# led.net
KiCad netlist of a schematic drawn in Altium Designer
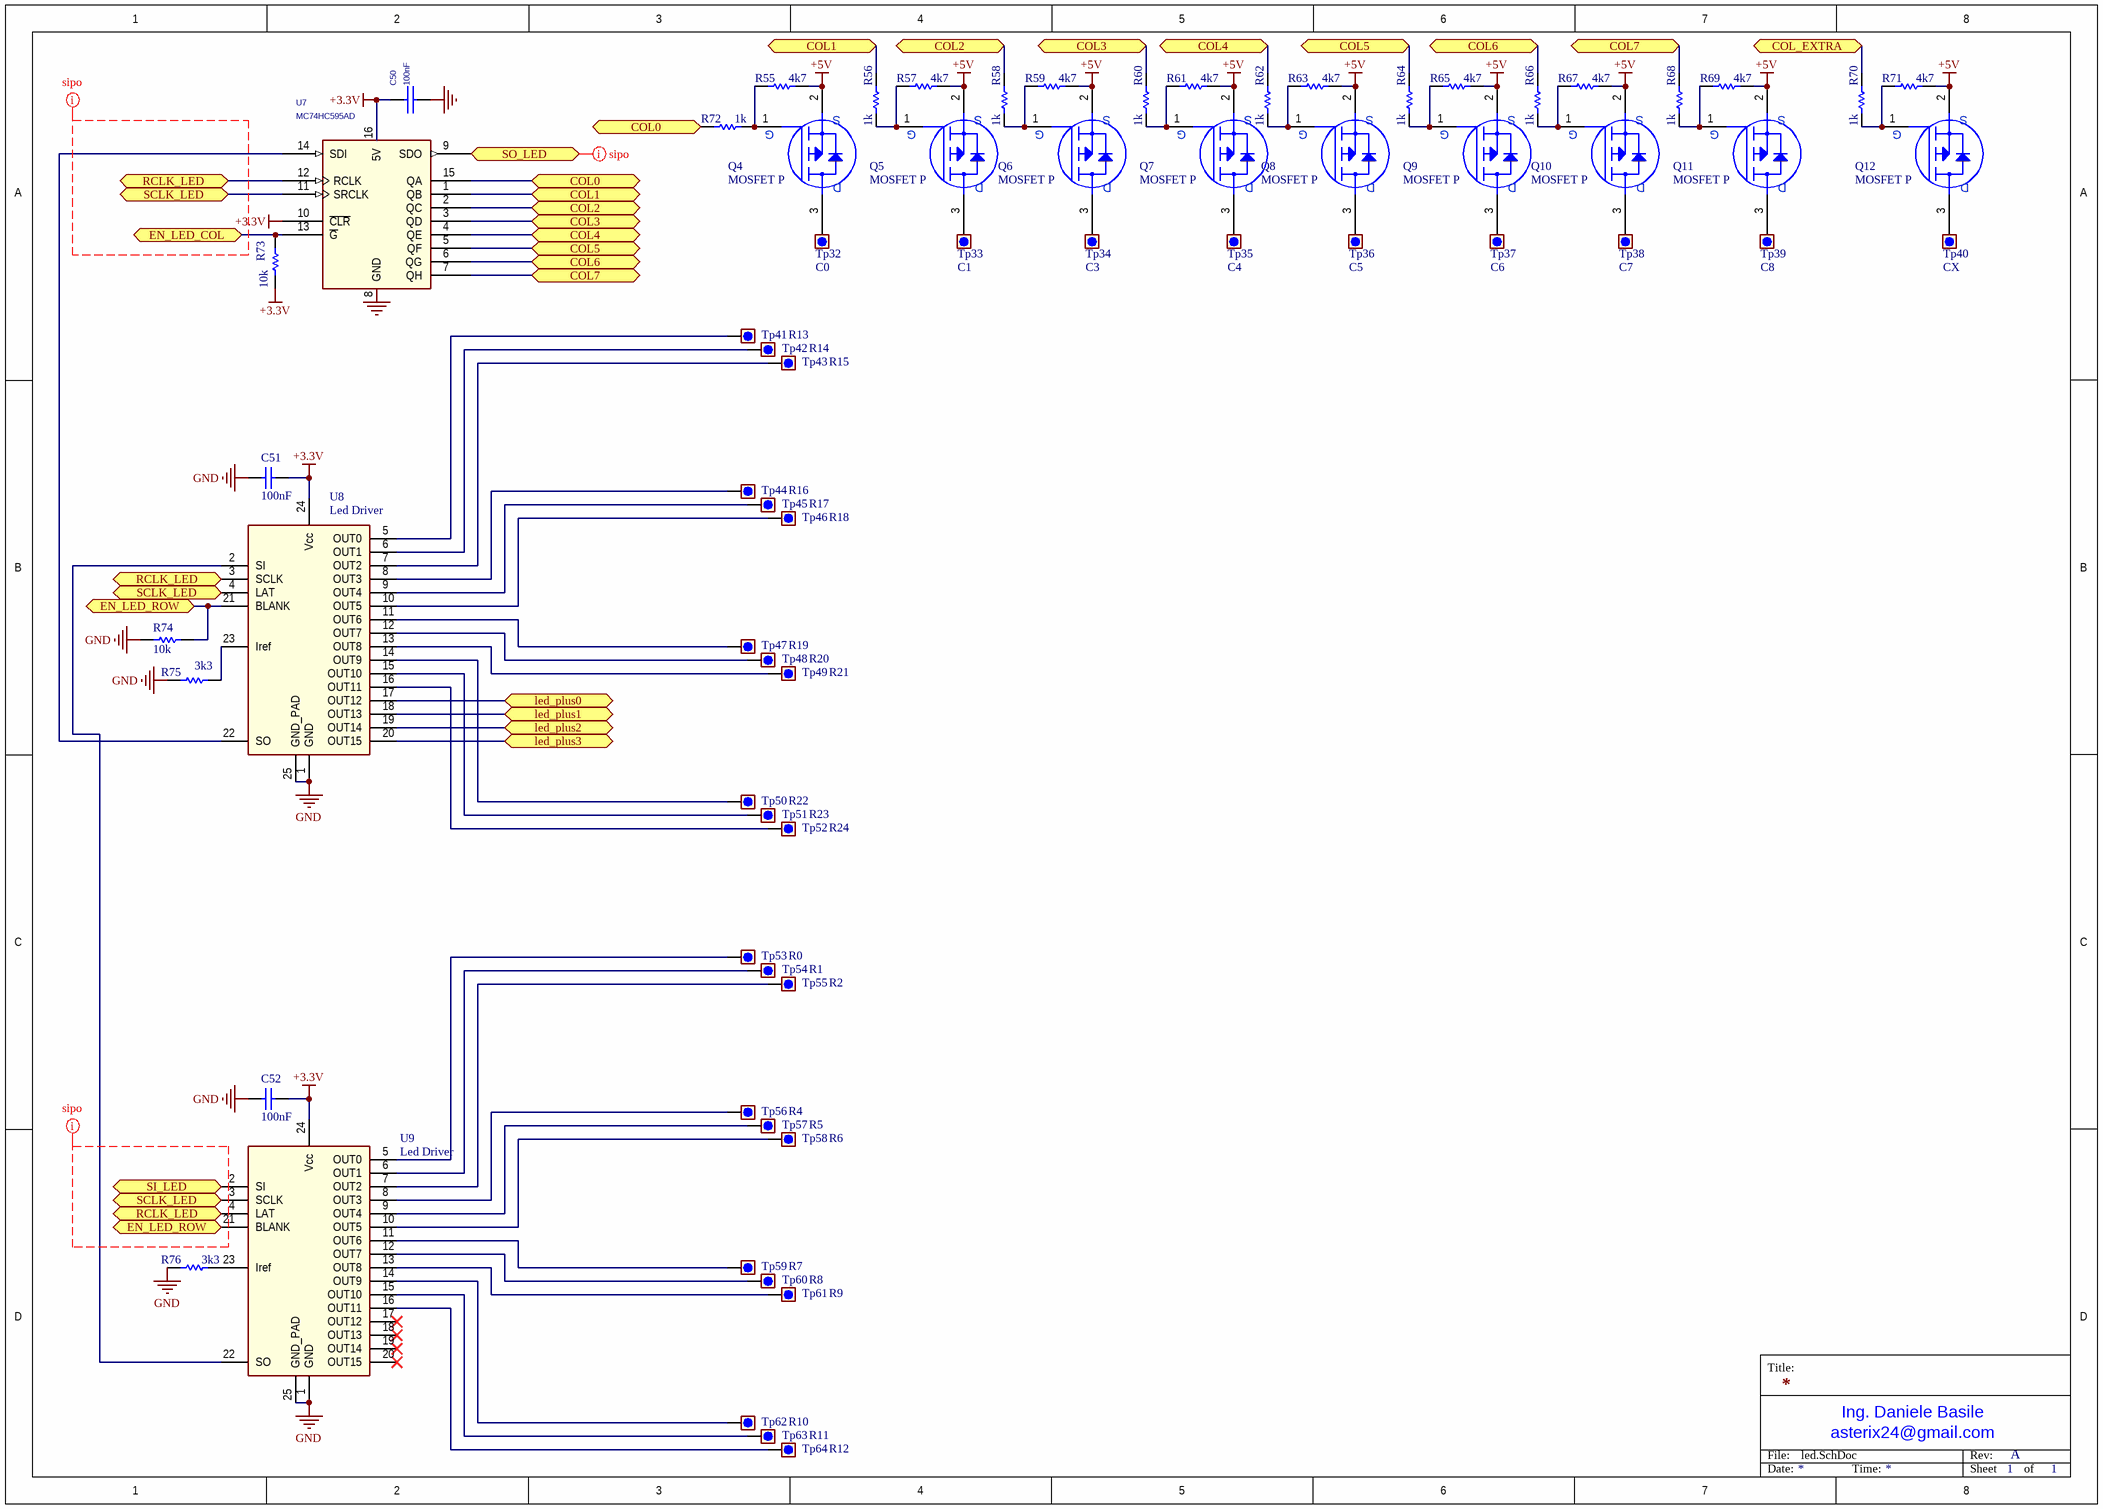
[diagram p0: led.SchDoc]

(export (version "E")
  (design (tool "Eeschema 10.0.6"))
  (components
    (comp (ref "C50")
      (value "100nF")
      (footprint "0603_[1608]")
      (description "CER 50V X7R")
      (libsource (lib "*") (part "C"))
    )
    (comp (ref "C51")
      (value "100nF")
      (footprint "0603_[1608]")
      (description "Ceramic X7R 50V")
      (fields (field (name "PUBLISHER") "Altium Limited"))
      (libsource (lib "DEVELER_Library") (part "Cap"))
    )
    (comp (ref "C52")
      (value "100nF")
      (footprint "0603_[1608]")
      (description "Ceramic X7R 50V")
      (fields (field (name "PUBLISHER") "Altium Limited"))
      (libsource (lib "DEVELER_Library") (part "Cap"))
    )
    (comp (ref "Q4")
      (value "MOSFET P")
      (footprint "SOT-23")
      (description "IRLML5103TRPbF; DMG1013UW;")
      (libsource (lib "develer_library") (part "MOSFET-P 3pin"))
    )
    (comp (ref "Q5")
      (value "MOSFET P")
      (footprint "SOT-23")
      (libsource (lib "develer_library") (part "MOSFET-P 3pin"))
    )
    (comp (ref "Q6")
      (value "MOSFET P")
      (footprint "SOT-23")
      (libsource (lib "develer_library") (part "MOSFET-P 3pin"))
    )
    (comp (ref "Q7")
      (value "MOSFET P")
      (footprint "SOT-23")
      (libsource (lib "develer_library") (part "MOSFET-P 3pin"))
    )
    (comp (ref "Q8")
      (value "MOSFET P")
      (footprint "SOT-23")
      (libsource (lib "develer_library") (part "MOSFET-P 3pin"))
    )
    (comp (ref "Q9")
      (value "MOSFET P")
      (footprint "SOT-23")
      (libsource (lib "develer_library") (part "MOSFET-P 3pin"))
    )
    (comp (ref "Q10")
      (value "MOSFET P")
      (footprint "SOT-23")
      (libsource (lib "develer_library") (part "MOSFET-P 3pin"))
    )
    (comp (ref "Q11")
      (value "MOSFET P")
      (footprint "SOT-23")
      (libsource (lib "develer_library") (part "MOSFET-P 3pin"))
    )
    (comp (ref "Q12")
      (value "MOSFET P")
      (footprint "SOT-23")
      (libsource (lib "develer_library") (part "MOSFET-P 3pin"))
    )
    (comp (ref "R55")
      (value "4k7")
      (footprint "0603_[1608]")
      (description "Resistor")
      (fields (field (name "PUBLISHER") "Altium Limited"))
      (libsource (lib "simboli") (part "Res1"))
    )
    (comp (ref "R56")
      (value "1k")
      (footprint "0603_[1608]")
      (description "Resistor")
      (fields (field (name "PUBLISHER") "Altium Limited"))
      (libsource (lib "simboli") (part "Res1"))
    )
    (comp (ref "R57")
      (value "4k7")
      (footprint "0603_[1608]")
      (description "Resistor")
      (fields (field (name "PUBLISHER") "Altium Limited"))
      (libsource (lib "simboli") (part "Res1"))
    )
    (comp (ref "R58")
      (value "1k")
      (footprint "0603_[1608]")
      (description "Resistor")
      (fields (field (name "PUBLISHER") "Altium Limited"))
      (libsource (lib "simboli") (part "Res1"))
    )
    (comp (ref "R59")
      (value "4k7")
      (footprint "0603_[1608]")
      (description "Resistor")
      (fields (field (name "PUBLISHER") "Altium Limited"))
      (libsource (lib "simboli") (part "Res1"))
    )
    (comp (ref "R60")
      (value "1k")
      (footprint "0603_[1608]")
      (description "Resistor")
      (fields (field (name "PUBLISHER") "Altium Limited"))
      (libsource (lib "simboli") (part "Res1"))
    )
    (comp (ref "R61")
      (value "4k7")
      (footprint "0603_[1608]")
      (description "Resistor")
      (fields (field (name "PUBLISHER") "Altium Limited"))
      (libsource (lib "simboli") (part "Res1"))
    )
    (comp (ref "R62")
      (value "1k")
      (footprint "0603_[1608]")
      (description "Resistor")
      (fields (field (name "PUBLISHER") "Altium Limited"))
      (libsource (lib "simboli") (part "Res1"))
    )
    (comp (ref "R63")
      (value "4k7")
      (footprint "0603_[1608]")
      (description "Resistor")
      (fields (field (name "PUBLISHER") "Altium Limited"))
      (libsource (lib "simboli") (part "Res1"))
    )
    (comp (ref "R64")
      (value "1k")
      (footprint "0603_[1608]")
      (description "Resistor")
      (fields (field (name "PUBLISHER") "Altium Limited"))
      (libsource (lib "simboli") (part "Res1"))
    )
    (comp (ref "R65")
      (value "4k7")
      (footprint "0603_[1608]")
      (description "Resistor")
      (fields (field (name "PUBLISHER") "Altium Limited"))
      (libsource (lib "simboli") (part "Res1"))
    )
    (comp (ref "R66")
      (value "1k")
      (footprint "0603_[1608]")
      (description "Resistor")
      (fields (field (name "PUBLISHER") "Altium Limited"))
      (libsource (lib "simboli") (part "Res1"))
    )
    (comp (ref "R67")
      (value "4k7")
      (footprint "0603_[1608]")
      (description "Resistor")
      (fields (field (name "PUBLISHER") "Altium Limited"))
      (libsource (lib "simboli") (part "Res1"))
    )
    (comp (ref "R68")
      (value "1k")
      (footprint "0603_[1608]")
      (description "Resistor")
      (fields (field (name "PUBLISHER") "Altium Limited"))
      (libsource (lib "simboli") (part "Res1"))
    )
    (comp (ref "R69")
      (value "4k7")
      (footprint "0603_[1608]")
      (description "Resistor")
      (fields (field (name "PUBLISHER") "Altium Limited"))
      (libsource (lib "simboli") (part "Res1"))
    )
    (comp (ref "R70")
      (value "1k")
      (footprint "0603_[1608]")
      (description "Resistor")
      (fields (field (name "PUBLISHER") "Altium Limited"))
      (libsource (lib "simboli") (part "Res1"))
    )
    (comp (ref "R71")
      (value "4k7")
      (footprint "0603_[1608]")
      (description "Resistor")
      (fields (field (name "PUBLISHER") "Altium Limited"))
      (libsource (lib "simboli") (part "Res1"))
    )
    (comp (ref "R72")
      (value "1k")
      (footprint "0603_[1608]")
      (description "Resistor")
      (fields (field (name "PUBLISHER") "Altium Limited"))
      (libsource (lib "simboli") (part "Res1"))
    )
    (comp (ref "R73")
      (value "10k")
      (footprint "0603_[1608]")
      (description "Resistor")
      (fields (field (name "PUBLISHER") "Altium Limited"))
      (libsource (lib "simboli") (part "Res1"))
    )
    (comp (ref "R74")
      (value "10k")
      (footprint "0603_[1608]")
      (description "Resistor")
      (fields (field (name "PUBLISHER") "Altium Limited"))
      (libsource (lib "simboli") (part "Res1"))
    )
    (comp (ref "R75")
      (value "3k3")
      (footprint "0805_[2012]")
      (description "Resistor")
      (fields (field (name "PUBLISHER") "Altium Limited"))
      (libsource (lib "simboli") (part "Res1"))
    )
    (comp (ref "R76")
      (value "3k3")
      (footprint "0805_[2012]")
      (description "Resistor")
      (fields (field (name "PUBLISHER") "Altium Limited"))
      (libsource (lib "simboli") (part "Res1"))
    )
    (comp (ref "Tp32")
      (value "C0")
      (footprint "TEST_POINT_THD_D1.6mm_oval")
      (description "Test point")
      (libsource (lib "") (part "Test_point_1"))
    )
    (comp (ref "Tp33")
      (value "C1")
      (footprint "TEST_POINT_THD_D1.6mm_oval")
      (description "Test point")
      (libsource (lib "") (part "Test_point_1"))
    )
    (comp (ref "Tp34")
      (value "C3")
      (footprint "TEST_POINT_THD_D1.6mm_oval")
      (description "Test point")
      (libsource (lib "") (part "Test_point_1"))
    )
    (comp (ref "Tp35")
      (value "C4")
      (footprint "TEST_POINT_THD_D1.6mm_oval")
      (description "Test point")
      (libsource (lib "") (part "Test_point_1"))
    )
    (comp (ref "Tp36")
      (value "C5")
      (footprint "TEST_POINT_THD_D1.6mm_oval")
      (description "Test point")
      (libsource (lib "") (part "Test_point_1"))
    )
    (comp (ref "Tp37")
      (value "C6")
      (footprint "TEST_POINT_THD_D1.6mm_oval")
      (description "Test point")
      (libsource (lib "") (part "Test_point_1"))
    )
    (comp (ref "Tp38")
      (value "C7")
      (footprint "TEST_POINT_THD_D1.6mm_oval")
      (description "Test point")
      (libsource (lib "") (part "Test_point_1"))
    )
    (comp (ref "Tp39")
      (value "C8")
      (footprint "TEST_POINT_THD_D1.6mm_oval")
      (description "Test point")
      (libsource (lib "") (part "Test_point_1"))
    )
    (comp (ref "Tp40")
      (value "CX")
      (footprint "TEST_POINT_THD_D1.6mm_oval")
      (description "Test point")
      (libsource (lib "") (part "Test_point_1"))
    )
    (comp (ref "Tp41")
      (value "R13")
      (footprint "TEST_POINT_THD_D1.6mm_oval")
      (description "Test point")
      (libsource (lib "DEVELER_Library") (part "Test_point"))
    )
    (comp (ref "Tp42")
      (value "R14")
      (footprint "TEST_POINT_THD_D1.6mm_oval")
      (description "Test point")
      (libsource (lib "DEVELER_Library") (part "Test_point"))
    )
    (comp (ref "Tp43")
      (value "R15")
      (footprint "TEST_POINT_THD_D1.6mm_oval")
      (description "Test point")
      (libsource (lib "DEVELER_Library") (part "Test_point"))
    )
    (comp (ref "Tp44")
      (value "R16")
      (footprint "TEST_POINT_THD_D1.6mm_oval")
      (description "Test point")
      (libsource (lib "DEVELER_Library") (part "Test_point"))
    )
    (comp (ref "Tp45")
      (value "R17")
      (footprint "TEST_POINT_THD_D1.6mm_oval")
      (description "Test point")
      (libsource (lib "DEVELER_Library") (part "Test_point"))
    )
    (comp (ref "Tp46")
      (value "R18")
      (footprint "TEST_POINT_THD_D1.6mm_oval")
      (description "Test point")
      (libsource (lib "DEVELER_Library") (part "Test_point"))
    )
    (comp (ref "Tp47")
      (value "R19")
      (footprint "TEST_POINT_THD_D1.6mm_oval")
      (description "Test point")
      (libsource (lib "DEVELER_Library") (part "Test_point"))
    )
    (comp (ref "Tp48")
      (value "R20")
      (footprint "TEST_POINT_THD_D1.6mm_oval")
      (description "Test point")
      (libsource (lib "DEVELER_Library") (part "Test_point"))
    )
    (comp (ref "Tp49")
      (value "R21")
      (footprint "TEST_POINT_THD_D1.6mm_oval")
      (description "Test point")
      (libsource (lib "DEVELER_Library") (part "Test_point"))
    )
    (comp (ref "Tp50")
      (value "R22")
      (footprint "TEST_POINT_THD_D1.6mm_oval")
      (description "Test point")
      (libsource (lib "DEVELER_Library") (part "Test_point"))
    )
    (comp (ref "Tp51")
      (value "R23")
      (footprint "TEST_POINT_THD_D1.6mm_oval")
      (description "Test point")
      (libsource (lib "DEVELER_Library") (part "Test_point"))
    )
    (comp (ref "Tp52")
      (value "R24")
      (footprint "TEST_POINT_THD_D1.6mm_oval")
      (description "Test point")
      (libsource (lib "DEVELER_Library") (part "Test_point"))
    )
    (comp (ref "Tp53")
      (value "R0")
      (footprint "TEST_POINT_THD_D1.6mm_oval")
      (description "Test point")
      (libsource (lib "DEVELER_Library") (part "Test_point"))
    )
    (comp (ref "Tp54")
      (value "R1")
      (footprint "TEST_POINT_THD_D1.6mm_oval")
      (description "Test point")
      (libsource (lib "DEVELER_Library") (part "Test_point"))
    )
    (comp (ref "Tp55")
      (value "R2")
      (footprint "TEST_POINT_THD_D1.6mm_oval")
      (description "Test point")
      (libsource (lib "DEVELER_Library") (part "Test_point"))
    )
    (comp (ref "Tp56")
      (value "R4")
      (footprint "TEST_POINT_THD_D1.6mm_oval")
      (description "Test point")
      (libsource (lib "DEVELER_Library") (part "Test_point"))
    )
    (comp (ref "Tp57")
      (value "R5")
      (footprint "TEST_POINT_THD_D1.6mm_oval")
      (description "Test point")
      (libsource (lib "DEVELER_Library") (part "Test_point"))
    )
    (comp (ref "Tp58")
      (value "R6")
      (footprint "TEST_POINT_THD_D1.6mm_oval")
      (description "Test point")
      (libsource (lib "DEVELER_Library") (part "Test_point"))
    )
    (comp (ref "Tp59")
      (value "R7")
      (footprint "TEST_POINT_THD_D1.6mm_oval")
      (description "Test point")
      (libsource (lib "DEVELER_Library") (part "Test_point"))
    )
    (comp (ref "Tp60")
      (value "R8")
      (footprint "TEST_POINT_THD_D1.6mm_oval")
      (description "Test point")
      (libsource (lib "DEVELER_Library") (part "Test_point"))
    )
    (comp (ref "Tp61")
      (value "R9")
      (footprint "TEST_POINT_THD_D1.6mm_oval")
      (description "Test point")
      (libsource (lib "DEVELER_Library") (part "Test_point"))
    )
    (comp (ref "Tp62")
      (value "R10")
      (footprint "TEST_POINT_THD_D1.6mm_oval")
      (description "Test point")
      (libsource (lib "DEVELER_Library") (part "Test_point"))
    )
    (comp (ref "Tp63")
      (value "R11")
      (footprint "TEST_POINT_THD_D1.6mm_oval")
      (description "Test point")
      (libsource (lib "DEVELER_Library") (part "Test_point"))
    )
    (comp (ref "Tp64")
      (value "R12")
      (footprint "TEST_POINT_THD_D1.6mm_oval")
      (description "Test point")
      (libsource (lib "DEVELER_Library") (part "Test_point"))
    )
    (comp (ref "U7")
      (value "MC74HC595AD")
      (footprint "SOIC16")
      (description "8-Bit Serial-Input/Serial or Prallel-Output Shift Register with Latched 3-State Outputs")
      (libsource (lib "*") (part "74HC595_27"))
    )
    (comp (ref "U8")
      (value "Led Driver")
      (footprint "TSOP65P640X120_HS-25N")
      (description "(Texas TLC5928; ST STP16CP05)")
      (libsource (lib "develer_library") (part "Led_driver"))
    )
    (comp (ref "U9")
      (value "Led Driver")
      (footprint "TSOP65P640X120_HS-25N")
      (description "(Texas TLC5928; ST STP16CP05)")
      (libsource (lib "develer_library") (part "Led_driver"))
    )
  )
  (nets
    (net (code "1") (name "+3.3V") (class "Default")
      (node (ref "C50") (pin "1") (pinfunction "1_1") (pintype "passive"))
      (node (ref "C51") (pin "2") (pinfunction "2_2") (pintype "passive"))
      (node (ref "C52") (pin "2") (pinfunction "2_2") (pintype "passive"))
      (node (ref "R73") (pin "1") (pinfunction "1_1") (pintype "passive"))
      (node (ref "U7") (pin "10") (pinfunction "~{CLR}_10") (pintype "passive"))
      (node (ref "U7") (pin "16") (pinfunction "5V_16") (pintype "power_in"))
      (node (ref "U8") (pin "24") (pinfunction "Vcc_24") (pintype "passive"))
      (node (ref "U9") (pin "24") (pinfunction "Vcc_24") (pintype "passive"))
    )
    (net (code "2") (name "+5V") (class "Default")
      (node (ref "Q10") (pin "2") (pinfunction "S_2") (pintype "passive"))
      (node (ref "Q11") (pin "2") (pinfunction "S_2") (pintype "passive"))
      (node (ref "Q12") (pin "2") (pinfunction "S_2") (pintype "passive"))
      (node (ref "Q4") (pin "2") (pinfunction "S_2") (pintype "passive"))
      (node (ref "Q5") (pin "2") (pinfunction "S_2") (pintype "passive"))
      (node (ref "Q6") (pin "2") (pinfunction "S_2") (pintype "passive"))
      (node (ref "Q7") (pin "2") (pinfunction "S_2") (pintype "passive"))
      (node (ref "Q8") (pin "2") (pinfunction "S_2") (pintype "passive"))
      (node (ref "Q9") (pin "2") (pinfunction "S_2") (pintype "passive"))
      (node (ref "R55") (pin "1") (pinfunction "1_1") (pintype "passive"))
      (node (ref "R57") (pin "1") (pinfunction "1_1") (pintype "passive"))
      (node (ref "R59") (pin "1") (pinfunction "1_1") (pintype "passive"))
      (node (ref "R61") (pin "1") (pinfunction "1_1") (pintype "passive"))
      (node (ref "R63") (pin "1") (pinfunction "1_1") (pintype "passive"))
      (node (ref "R65") (pin "1") (pinfunction "1_1") (pintype "passive"))
      (node (ref "R67") (pin "1") (pinfunction "1_1") (pintype "passive"))
      (node (ref "R69") (pin "1") (pinfunction "1_1") (pintype "passive"))
      (node (ref "R71") (pin "1") (pinfunction "1_1") (pintype "passive"))
    )
    (net (code "3") (name "/COL0") (class "Default")
      (node (ref "R72") (pin "2") (pinfunction "2_2") (pintype "passive"))
      (node (ref "U7") (pin "15") (pinfunction "QA_15") (pintype "tri_state"))
    )
    (net (code "4") (name "/COL1") (class "Default")
      (node (ref "R56") (pin "1") (pinfunction "1_1") (pintype "passive"))
      (node (ref "U7") (pin "1") (pinfunction "QB_1") (pintype "tri_state"))
    )
    (net (code "5") (name "/COL2") (class "Default")
      (node (ref "R58") (pin "1") (pinfunction "1_1") (pintype "passive"))
      (node (ref "U7") (pin "2") (pinfunction "QC_2") (pintype "tri_state"))
    )
    (net (code "6") (name "/COL3") (class "Default")
      (node (ref "R60") (pin "1") (pinfunction "1_1") (pintype "passive"))
      (node (ref "U7") (pin "3") (pinfunction "QD_3") (pintype "tri_state"))
    )
    (net (code "7") (name "/COL4") (class "Default")
      (node (ref "R62") (pin "1") (pinfunction "1_1") (pintype "passive"))
      (node (ref "U7") (pin "4") (pinfunction "QE_4") (pintype "tri_state"))
    )
    (net (code "8") (name "/COL5") (class "Default")
      (node (ref "R64") (pin "1") (pinfunction "1_1") (pintype "passive"))
      (node (ref "U7") (pin "5") (pinfunction "QF_5") (pintype "tri_state"))
    )
    (net (code "9") (name "/COL6") (class "Default")
      (node (ref "R66") (pin "1") (pinfunction "1_1") (pintype "passive"))
      (node (ref "U7") (pin "6") (pinfunction "QG_6") (pintype "tri_state"))
    )
    (net (code "10") (name "/COL7") (class "Default")
      (node (ref "R68") (pin "1") (pinfunction "1_1") (pintype "passive"))
      (node (ref "U7") (pin "7") (pinfunction "QH_7") (pintype "tri_state"))
    )
    (net (code "11") (name "/COL_EXTRA") (class "Default")
      (node (ref "R70") (pin "1") (pinfunction "1_1") (pintype "passive"))
    )
    (net (code "12") (name "/EN_LED_COL") (class "Default")
      (node (ref "R73") (pin "2") (pinfunction "2_2") (pintype "passive"))
      (node (ref "U7") (pin "13") (pinfunction "~{G}_13") (pintype "passive"))
    )
    (net (code "13") (name "/EN_LED_ROW") (class "Default")
      (node (ref "R74") (pin "2") (pinfunction "2_2") (pintype "passive"))
      (node (ref "U8") (pin "21") (pinfunction "BLANK_21") (pintype "passive"))
      (node (ref "U9") (pin "21") (pinfunction "BLANK_21") (pintype "passive"))
    )
    (net (code "14") (name "/RCLK_LED") (class "Default")
      (node (ref "U7") (pin "12") (pinfunction "RCLK_12") (pintype "input"))
      (node (ref "U8") (pin "3") (pinfunction "SCLK_3") (pintype "passive"))
      (node (ref "U9") (pin "4") (pinfunction "LAT_4") (pintype "passive"))
    )
    (net (code "15") (name "/SCLK_LED") (class "Default")
      (node (ref "U7") (pin "11") (pinfunction "SRCLK_11") (pintype "input"))
      (node (ref "U8") (pin "4") (pinfunction "LAT_4") (pintype "passive"))
      (node (ref "U9") (pin "3") (pinfunction "SCLK_3") (pintype "passive"))
    )
    (net (code "16") (name "/SI_LED") (class "Default")
      (node (ref "U9") (pin "2") (pinfunction "SI_2") (pintype "passive"))
    )
    (net (code "17") (name "/SO_LED") (class "Default")
      (node (ref "U7") (pin "9") (pinfunction "SDO_9") (pintype "output"))
    )
    (net (code "18") (name "/led_plus0") (class "Default")
      (node (ref "U8") (pin "17") (pinfunction "OUT12_17") (pintype "passive"))
    )
    (net (code "19") (name "/led_plus1") (class "Default")
      (node (ref "U8") (pin "18") (pinfunction "OUT13_18") (pintype "passive"))
    )
    (net (code "20") (name "/led_plus2") (class "Default")
      (node (ref "U8") (pin "19") (pinfunction "OUT14_19") (pintype "passive"))
    )
    (net (code "21") (name "/led_plus3") (class "Default")
      (node (ref "U8") (pin "20") (pinfunction "OUT15_20") (pintype "passive"))
    )
    (net (code "22") (name "GND") (class "Default")
      (node (ref "C50") (pin "2") (pinfunction "2_2") (pintype "passive"))
      (node (ref "C51") (pin "1") (pinfunction "1_1") (pintype "passive"))
      (node (ref "C52") (pin "1") (pinfunction "1_1") (pintype "passive"))
      (node (ref "R74") (pin "1") (pinfunction "1_1") (pintype "passive"))
      (node (ref "R75") (pin "1") (pinfunction "1_1") (pintype "passive"))
      (node (ref "R76") (pin "1") (pinfunction "1_1") (pintype "passive"))
      (node (ref "U7") (pin "8") (pinfunction "GND_8") (pintype "power_in"))
      (node (ref "U8") (pin "1") (pinfunction "GND_1") (pintype "passive"))
      (node (ref "U8") (pin "25") (pinfunction "GND_PAD_25") (pintype "passive"))
      (node (ref "U9") (pin "1") (pinfunction "GND_1") (pintype "passive"))
      (node (ref "U9") (pin "25") (pinfunction "GND_PAD_25") (pintype "passive"))
    )
    (net (code "23") (name "Net-(Q4-D)") (class "Default")
      (node (ref "Q4") (pin "3") (pinfunction "D_3") (pintype "passive"))
      (node (ref "Tp32") (pin "1") (pinfunction "1_1") (pintype "passive"))
    )
    (net (code "24") (name "Net-(Q4-G)") (class "Default")
      (node (ref "Q4") (pin "1") (pinfunction "G_1") (pintype "passive"))
      (node (ref "R55") (pin "2") (pinfunction "2_2") (pintype "passive"))
      (node (ref "R72") (pin "1") (pinfunction "1_1") (pintype "passive"))
    )
    (net (code "25") (name "Net-(Q5-D)") (class "Default")
      (node (ref "Q5") (pin "3") (pinfunction "D_3") (pintype "passive"))
      (node (ref "Tp33") (pin "1") (pinfunction "1_1") (pintype "passive"))
    )
    (net (code "26") (name "Net-(Q5-G)") (class "Default")
      (node (ref "Q5") (pin "1") (pinfunction "G_1") (pintype "passive"))
      (node (ref "R56") (pin "2") (pinfunction "2_2") (pintype "passive"))
      (node (ref "R57") (pin "2") (pinfunction "2_2") (pintype "passive"))
    )
    (net (code "27") (name "Net-(Q6-D)") (class "Default")
      (node (ref "Q6") (pin "3") (pinfunction "D_3") (pintype "passive"))
      (node (ref "Tp34") (pin "1") (pinfunction "1_1") (pintype "passive"))
    )
    (net (code "28") (name "Net-(Q6-G)") (class "Default")
      (node (ref "Q6") (pin "1") (pinfunction "G_1") (pintype "passive"))
      (node (ref "R58") (pin "2") (pinfunction "2_2") (pintype "passive"))
      (node (ref "R59") (pin "2") (pinfunction "2_2") (pintype "passive"))
    )
    (net (code "29") (name "Net-(Q7-D)") (class "Default")
      (node (ref "Q7") (pin "3") (pinfunction "D_3") (pintype "passive"))
      (node (ref "Tp35") (pin "1") (pinfunction "1_1") (pintype "passive"))
    )
    (net (code "30") (name "Net-(Q7-G)") (class "Default")
      (node (ref "Q7") (pin "1") (pinfunction "G_1") (pintype "passive"))
      (node (ref "R60") (pin "2") (pinfunction "2_2") (pintype "passive"))
      (node (ref "R61") (pin "2") (pinfunction "2_2") (pintype "passive"))
    )
    (net (code "31") (name "Net-(Q8-D)") (class "Default")
      (node (ref "Q8") (pin "3") (pinfunction "D_3") (pintype "passive"))
      (node (ref "Tp36") (pin "1") (pinfunction "1_1") (pintype "passive"))
    )
    (net (code "32") (name "Net-(Q8-G)") (class "Default")
      (node (ref "Q8") (pin "1") (pinfunction "G_1") (pintype "passive"))
      (node (ref "R62") (pin "2") (pinfunction "2_2") (pintype "passive"))
      (node (ref "R63") (pin "2") (pinfunction "2_2") (pintype "passive"))
    )
    (net (code "33") (name "Net-(Q9-D)") (class "Default")
      (node (ref "Q9") (pin "3") (pinfunction "D_3") (pintype "passive"))
      (node (ref "Tp37") (pin "1") (pinfunction "1_1") (pintype "passive"))
    )
    (net (code "34") (name "Net-(Q9-G)") (class "Default")
      (node (ref "Q9") (pin "1") (pinfunction "G_1") (pintype "passive"))
      (node (ref "R64") (pin "2") (pinfunction "2_2") (pintype "passive"))
      (node (ref "R65") (pin "2") (pinfunction "2_2") (pintype "passive"))
    )
    (net (code "35") (name "Net-(Q10-D)") (class "Default")
      (node (ref "Q10") (pin "3") (pinfunction "D_3") (pintype "passive"))
      (node (ref "Tp38") (pin "1") (pinfunction "1_1") (pintype "passive"))
    )
    (net (code "36") (name "Net-(Q10-G)") (class "Default")
      (node (ref "Q10") (pin "1") (pinfunction "G_1") (pintype "passive"))
      (node (ref "R66") (pin "2") (pinfunction "2_2") (pintype "passive"))
      (node (ref "R67") (pin "2") (pinfunction "2_2") (pintype "passive"))
    )
    (net (code "37") (name "Net-(Q11-D)") (class "Default")
      (node (ref "Q11") (pin "3") (pinfunction "D_3") (pintype "passive"))
      (node (ref "Tp39") (pin "1") (pinfunction "1_1") (pintype "passive"))
    )
    (net (code "38") (name "Net-(Q11-G)") (class "Default")
      (node (ref "Q11") (pin "1") (pinfunction "G_1") (pintype "passive"))
      (node (ref "R68") (pin "2") (pinfunction "2_2") (pintype "passive"))
      (node (ref "R69") (pin "2") (pinfunction "2_2") (pintype "passive"))
    )
    (net (code "39") (name "Net-(Q12-D)") (class "Default")
      (node (ref "Q12") (pin "3") (pinfunction "D_3") (pintype "passive"))
      (node (ref "Tp40") (pin "1") (pinfunction "1_1") (pintype "passive"))
    )
    (net (code "40") (name "Net-(Q12-G)") (class "Default")
      (node (ref "Q12") (pin "1") (pinfunction "G_1") (pintype "passive"))
      (node (ref "R70") (pin "2") (pinfunction "2_2") (pintype "passive"))
      (node (ref "R71") (pin "2") (pinfunction "2_2") (pintype "passive"))
    )
    (net (code "41") (name "Net-(U7-SDI)") (class "Default")
      (node (ref "U7") (pin "14") (pinfunction "SDI_14") (pintype "input"))
      (node (ref "U8") (pin "22") (pinfunction "SO_22") (pintype "passive"))
    )
    (net (code "42") (name "Net-(U8-Iref)") (class "Default")
      (node (ref "R75") (pin "2") (pinfunction "2_2") (pintype "passive"))
      (node (ref "U8") (pin "23") (pinfunction "Iref_23") (pintype "passive"))
    )
    (net (code "43") (name "Net-(U8-OUT0)") (class "Default")
      (node (ref "Tp41") (pin "1") (pinfunction "1_1") (pintype "passive"))
      (node (ref "U8") (pin "5") (pinfunction "OUT0_5") (pintype "passive"))
    )
    (net (code "44") (name "Net-(U8-OUT1)") (class "Default")
      (node (ref "Tp42") (pin "1") (pinfunction "1_1") (pintype "passive"))
      (node (ref "U8") (pin "6") (pinfunction "OUT1_6") (pintype "passive"))
    )
    (net (code "45") (name "Net-(U8-OUT2)") (class "Default")
      (node (ref "Tp43") (pin "1") (pinfunction "1_1") (pintype "passive"))
      (node (ref "U8") (pin "7") (pinfunction "OUT2_7") (pintype "passive"))
    )
    (net (code "46") (name "Net-(U8-OUT3)") (class "Default")
      (node (ref "Tp44") (pin "1") (pinfunction "1_1") (pintype "passive"))
      (node (ref "U8") (pin "8") (pinfunction "OUT3_8") (pintype "passive"))
    )
    (net (code "47") (name "Net-(U8-OUT4)") (class "Default")
      (node (ref "Tp45") (pin "1") (pinfunction "1_1") (pintype "passive"))
      (node (ref "U8") (pin "9") (pinfunction "OUT4_9") (pintype "passive"))
    )
    (net (code "48") (name "Net-(U8-OUT5)") (class "Default")
      (node (ref "Tp46") (pin "1") (pinfunction "1_1") (pintype "passive"))
      (node (ref "U8") (pin "10") (pinfunction "OUT5_10") (pintype "passive"))
    )
    (net (code "49") (name "Net-(U8-OUT6)") (class "Default")
      (node (ref "Tp47") (pin "1") (pinfunction "1_1") (pintype "passive"))
      (node (ref "U8") (pin "11") (pinfunction "OUT6_11") (pintype "passive"))
    )
    (net (code "50") (name "Net-(U8-OUT7)") (class "Default")
      (node (ref "Tp48") (pin "1") (pinfunction "1_1") (pintype "passive"))
      (node (ref "U8") (pin "12") (pinfunction "OUT7_12") (pintype "passive"))
    )
    (net (code "51") (name "Net-(U8-OUT8)") (class "Default")
      (node (ref "Tp49") (pin "1") (pinfunction "1_1") (pintype "passive"))
      (node (ref "U8") (pin "13") (pinfunction "OUT8_13") (pintype "passive"))
    )
    (net (code "52") (name "Net-(U8-OUT9)") (class "Default")
      (node (ref "Tp50") (pin "1") (pinfunction "1_1") (pintype "passive"))
      (node (ref "U8") (pin "14") (pinfunction "OUT9_14") (pintype "passive"))
    )
    (net (code "53") (name "Net-(U8-OUT10)") (class "Default")
      (node (ref "Tp51") (pin "1") (pinfunction "1_1") (pintype "passive"))
      (node (ref "U8") (pin "15") (pinfunction "OUT10_15") (pintype "passive"))
    )
    (net (code "54") (name "Net-(U8-OUT11)") (class "Default")
      (node (ref "Tp52") (pin "1") (pinfunction "1_1") (pintype "passive"))
      (node (ref "U8") (pin "16") (pinfunction "OUT11_16") (pintype "passive"))
    )
    (net (code "55") (name "Net-(U8-SI)") (class "Default")
      (node (ref "U8") (pin "2") (pinfunction "SI_2") (pintype "passive"))
      (node (ref "U9") (pin "22") (pinfunction "SO_22") (pintype "passive"))
    )
    (net (code "56") (name "Net-(U9-Iref)") (class "Default")
      (node (ref "R76") (pin "2") (pinfunction "2_2") (pintype "passive"))
      (node (ref "U9") (pin "23") (pinfunction "Iref_23") (pintype "passive"))
    )
    (net (code "57") (name "Net-(U9-OUT0)") (class "Default")
      (node (ref "Tp53") (pin "1") (pinfunction "1_1") (pintype "passive"))
      (node (ref "U9") (pin "5") (pinfunction "OUT0_5") (pintype "passive"))
    )
    (net (code "58") (name "Net-(U9-OUT1)") (class "Default")
      (node (ref "Tp54") (pin "1") (pinfunction "1_1") (pintype "passive"))
      (node (ref "U9") (pin "6") (pinfunction "OUT1_6") (pintype "passive"))
    )
    (net (code "59") (name "Net-(U9-OUT2)") (class "Default")
      (node (ref "Tp55") (pin "1") (pinfunction "1_1") (pintype "passive"))
      (node (ref "U9") (pin "7") (pinfunction "OUT2_7") (pintype "passive"))
    )
    (net (code "60") (name "Net-(U9-OUT3)") (class "Default")
      (node (ref "Tp56") (pin "1") (pinfunction "1_1") (pintype "passive"))
      (node (ref "U9") (pin "8") (pinfunction "OUT3_8") (pintype "passive"))
    )
    (net (code "61") (name "Net-(U9-OUT4)") (class "Default")
      (node (ref "Tp57") (pin "1") (pinfunction "1_1") (pintype "passive"))
      (node (ref "U9") (pin "9") (pinfunction "OUT4_9") (pintype "passive"))
    )
    (net (code "62") (name "Net-(U9-OUT5)") (class "Default")
      (node (ref "Tp58") (pin "1") (pinfunction "1_1") (pintype "passive"))
      (node (ref "U9") (pin "10") (pinfunction "OUT5_10") (pintype "passive"))
    )
    (net (code "63") (name "Net-(U9-OUT6)") (class "Default")
      (node (ref "Tp59") (pin "1") (pinfunction "1_1") (pintype "passive"))
      (node (ref "U9") (pin "11") (pinfunction "OUT6_11") (pintype "passive"))
    )
    (net (code "64") (name "Net-(U9-OUT7)") (class "Default")
      (node (ref "Tp60") (pin "1") (pinfunction "1_1") (pintype "passive"))
      (node (ref "U9") (pin "12") (pinfunction "OUT7_12") (pintype "passive"))
    )
    (net (code "65") (name "Net-(U9-OUT8)") (class "Default")
      (node (ref "Tp61") (pin "1") (pinfunction "1_1") (pintype "passive"))
      (node (ref "U9") (pin "13") (pinfunction "OUT8_13") (pintype "passive"))
    )
    (net (code "66") (name "Net-(U9-OUT9)") (class "Default")
      (node (ref "Tp62") (pin "1") (pinfunction "1_1") (pintype "passive"))
      (node (ref "U9") (pin "14") (pinfunction "OUT9_14") (pintype "passive"))
    )
    (net (code "67") (name "Net-(U9-OUT10)") (class "Default")
      (node (ref "Tp63") (pin "1") (pinfunction "1_1") (pintype "passive"))
      (node (ref "U9") (pin "15") (pinfunction "OUT10_15") (pintype "passive"))
    )
    (net (code "68") (name "Net-(U9-OUT11)") (class "Default")
      (node (ref "Tp64") (pin "1") (pinfunction "1_1") (pintype "passive"))
      (node (ref "U9") (pin "16") (pinfunction "OUT11_16") (pintype "passive"))
    )
    (net (code "69") (name "unconnected-(U9-OUT12-Pad17)") (class "Default")
      (node (ref "U9") (pin "17") (pinfunction "OUT12_17") (pintype "passive+no_connect"))
    )
    (net (code "70") (name "unconnected-(U9-OUT13-Pad18)") (class "Default")
      (node (ref "U9") (pin "18") (pinfunction "OUT13_18") (pintype "passive+no_connect"))
    )
    (net (code "71") (name "unconnected-(U9-OUT14-Pad19)") (class "Default")
      (node (ref "U9") (pin "19") (pinfunction "OUT14_19") (pintype "passive+no_connect"))
    )
    (net (code "72") (name "unconnected-(U9-OUT15-Pad20)") (class "Default")
      (node (ref "U9") (pin "20") (pinfunction "OUT15_20") (pintype "passive+no_connect"))
    )
  )
)
